# LCD.net
KiCad netlist of a schematic drawn in Altium Designer
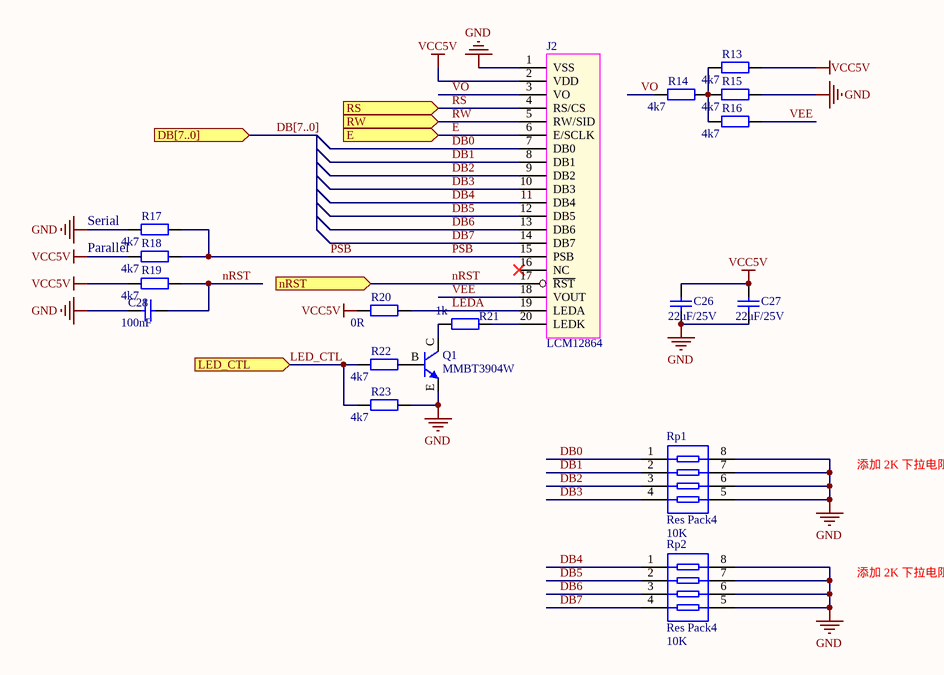
[diagram p0: LCD.SchDoc]

(export (version "E")
  (design (tool "Eeschema 10.0.6"))
  (components
    (comp (ref "C26") (value "22uF/25V") (footprint "C0805") (libsource (lib "myPCB") (part "CAP_08")))
    (comp (ref "C27") (value "22uF/25V") (footprint "C0805") (libsource (lib "myPCB") (part "CAP_08")))
    (comp (ref "C28") (value "100nF") (footprint "R0603") (libsource (lib "MyYX") (part "CAP_04")))
    (comp (ref "J2")
      (value "LCM12864")
      (footprint "LCD12864")
      (description "ST7920/LCM12864")
      (libsource (lib "MyYX") (part "LCM12864"))
    )
    (comp (ref "Q1") (value "MMBT3904W") (footprint "SOT_23") (libsource (lib "MyYX") (part "MMBT3904TT1G")))
    (comp (ref "R13") (value "4k7") (footprint "R0603") (libsource (lib "MyYX") (part "RES_04")))
    (comp (ref "R14") (value "4k7") (footprint "R0603") (libsource (lib "MyYX") (part "RES_04")))
    (comp (ref "R15") (value "4k7") (footprint "R0603") (libsource (lib "MyYX") (part "RES_04")))
    (comp (ref "R16") (value "4k7") (footprint "R0603") (libsource (lib "MyYX") (part "RES_04")))
    (comp (ref "R17") (value "4k7") (footprint "R0603") (libsource (lib "MyYX") (part "RES_04")))
    (comp (ref "R18") (value "4k7") (footprint "R0603") (libsource (lib "MyYX") (part "RES_04")))
    (comp (ref "R19") (value "4k7") (footprint "R0603") (libsource (lib "MyYX") (part "RES_04")))
    (comp (ref "R20") (value "0R") (footprint "R0603") (libsource (lib "MyYX") (part "RES_04")))
    (comp (ref "R21") (value "1k") (footprint "R0603") (libsource (lib "MyYX") (part "RES_04")))
    (comp (ref "R22") (value "4k7") (footprint "R0603") (libsource (lib "MyYX") (part "RES_04")))
    (comp (ref "R23") (value "4k7") (footprint "R0603") (libsource (lib "MyYX") (part "RES_04")))
    (comp (ref "Rp1")
      (value "Res Pack4")
      (footprint "0603X4")
      (fields (field (name "ALTIUM_VALUE") "10K"))
      (libsource (lib "MAX51") (part "Res Pack4"))
    )
    (comp (ref "Rp2")
      (value "Res Pack4")
      (footprint "0603X4")
      (fields (field (name "ALTIUM_VALUE") "10K"))
      (libsource (lib "MAX51") (part "Res Pack4"))
    )
  )
  (nets
    (net (code "1") (name "/DB0") (class "Default")
      (node (ref "J2") (pin "7") (pinfunction "DB0_7") (pintype "passive"))
      (node (ref "Rp1") (pin "1") (pinfunction "1_1") (pintype "passive"))
    )
    (net (code "2") (name "/DB1") (class "Default")
      (node (ref "J2") (pin "8") (pinfunction "DB1_8") (pintype "passive"))
      (node (ref "Rp1") (pin "2") (pinfunction "2_2") (pintype "passive"))
    )
    (net (code "3") (name "/DB2") (class "Default")
      (node (ref "J2") (pin "9") (pinfunction "DB2_9") (pintype "passive"))
      (node (ref "Rp1") (pin "3") (pinfunction "3_3") (pintype "passive"))
    )
    (net (code "4") (name "/DB3") (class "Default")
      (node (ref "J2") (pin "10") (pinfunction "DB3_10") (pintype "passive"))
      (node (ref "Rp1") (pin "4") (pinfunction "4_4") (pintype "passive"))
    )
    (net (code "5") (name "/DB4") (class "Default")
      (node (ref "J2") (pin "11") (pinfunction "DB4_11") (pintype "passive"))
      (node (ref "Rp2") (pin "1") (pinfunction "1_1") (pintype "passive"))
    )
    (net (code "6") (name "/DB5") (class "Default")
      (node (ref "J2") (pin "12") (pinfunction "DB5_12") (pintype "passive"))
      (node (ref "Rp2") (pin "2") (pinfunction "2_2") (pintype "passive"))
    )
    (net (code "7") (name "/DB6") (class "Default")
      (node (ref "J2") (pin "13") (pinfunction "DB6_13") (pintype "passive"))
      (node (ref "Rp2") (pin "3") (pinfunction "3_3") (pintype "passive"))
    )
    (net (code "8") (name "/DB7") (class "Default")
      (node (ref "J2") (pin "14") (pinfunction "DB7_14") (pintype "passive"))
      (node (ref "Rp2") (pin "4") (pinfunction "4_4") (pintype "passive"))
    )
    (net (code "10") (name "/E") (class "Default")
      (node (ref "J2") (pin "6") (pinfunction "E/SCLK_6") (pintype "passive"))
    )
    (net (code "11") (name "/LEDA") (class "Default")
      (node (ref "J2") (pin "19") (pinfunction "LEDA_19") (pintype "passive"))
      (node (ref "R20") (pin "2") (pinfunction "2_2") (pintype "passive"))
    )
    (net (code "12") (name "/LED_CTL") (class "Default")
      (node (ref "R22") (pin "1") (pinfunction "1_1") (pintype "passive"))
      (node (ref "R23") (pin "1") (pinfunction "1_1") (pintype "passive"))
    )
    (net (code "13") (name "/PSB") (class "Default")
      (node (ref "J2") (pin "15") (pinfunction "PSB_15") (pintype "passive"))
      (node (ref "R17") (pin "2") (pinfunction "2_2") (pintype "passive"))
      (node (ref "R18") (pin "2") (pinfunction "2_2") (pintype "passive"))
    )
    (net (code "14") (name "/RS") (class "Default")
      (node (ref "J2") (pin "4") (pinfunction "RS/CS_4") (pintype "passive"))
    )
    (net (code "15") (name "/RW") (class "Default")
      (node (ref "J2") (pin "5") (pinfunction "RW/SID_5") (pintype "passive"))
    )
    (net (code "16") (name "/VEE") (class "Default")
      (node (ref "J2") (pin "18") (pinfunction "VOUT_18") (pintype "passive"))
      (node (ref "R16") (pin "2") (pinfunction "2_2") (pintype "passive"))
    )
    (net (code "17") (name "/VO") (class "Default")
      (node (ref "J2") (pin "3") (pinfunction "VO_3") (pintype "passive"))
      (node (ref "R14") (pin "1") (pinfunction "1_1") (pintype "passive"))
    )
    (net (code "18") (name "/nRST") (class "Default")
      (node (ref "C28") (pin "2") (pinfunction "2_2") (pintype "passive"))
      (node (ref "J2") (pin "17") (pinfunction "~{RST}_17") (pintype "passive"))
      (node (ref "R19") (pin "2") (pinfunction "2_2") (pintype "passive"))
    )
    (net (code "19") (name "GND") (class "Default")
      (node (ref "C26") (pin "1") (pinfunction "1_1") (pintype "passive"))
      (node (ref "C27") (pin "1") (pinfunction "1_1") (pintype "passive"))
      (node (ref "C28") (pin "1") (pinfunction "1_1") (pintype "passive"))
      (node (ref "J2") (pin "1") (pinfunction "VSS_1") (pintype "passive"))
      (node (ref "Q1") (pin "E") (pinfunction "E_E") (pintype "passive"))
      (node (ref "R15") (pin "2") (pinfunction "2_2") (pintype "passive"))
      (node (ref "R17") (pin "1") (pinfunction "1_1") (pintype "passive"))
      (node (ref "R23") (pin "2") (pinfunction "2_2") (pintype "passive"))
      (node (ref "Rp1") (pin "5") (pinfunction "5_5") (pintype "passive"))
      (node (ref "Rp1") (pin "6") (pinfunction "6_6") (pintype "passive"))
      (node (ref "Rp1") (pin "7") (pinfunction "7_7") (pintype "passive"))
      (node (ref "Rp1") (pin "8") (pinfunction "8_8") (pintype "passive"))
      (node (ref "Rp2") (pin "5") (pinfunction "5_5") (pintype "passive"))
      (node (ref "Rp2") (pin "6") (pinfunction "6_6") (pintype "passive"))
      (node (ref "Rp2") (pin "7") (pinfunction "7_7") (pintype "passive"))
      (node (ref "Rp2") (pin "8") (pinfunction "8_8") (pintype "passive"))
    )
    (net (code "20") (name "Net-(J2-LEDK)") (class "Default")
      (node (ref "J2") (pin "20") (pinfunction "LEDK_20") (pintype "passive"))
      (node (ref "R21") (pin "2") (pinfunction "2_2") (pintype "passive"))
    )
    (net (code "21") (name "Net-(Q1-PadB)") (class "Default")
      (node (ref "Q1") (pin "B") (pinfunction "B_B") (pintype "passive"))
      (node (ref "R22") (pin "2") (pinfunction "2_2") (pintype "passive"))
    )
    (net (code "22") (name "Net-(Q1-PadC)") (class "Default")
      (node (ref "Q1") (pin "C") (pinfunction "C_C") (pintype "passive"))
      (node (ref "R21") (pin "1") (pinfunction "1_1") (pintype "passive"))
    )
    (net (code "23") (name "Net-(R13-Pad1)") (class "Default")
      (node (ref "R13") (pin "1") (pinfunction "1_1") (pintype "passive"))
      (node (ref "R14") (pin "2") (pinfunction "2_2") (pintype "passive"))
      (node (ref "R15") (pin "1") (pinfunction "1_1") (pintype "passive"))
      (node (ref "R16") (pin "1") (pinfunction "1_1") (pintype "passive"))
    )
    (net (code "24") (name "VCC5V") (class "Default")
      (node (ref "C26") (pin "2") (pinfunction "2_2") (pintype "passive"))
      (node (ref "C27") (pin "2") (pinfunction "2_2") (pintype "passive"))
      (node (ref "J2") (pin "2") (pinfunction "VDD_2") (pintype "passive"))
      (node (ref "R13") (pin "2") (pinfunction "2_2") (pintype "passive"))
      (node (ref "R18") (pin "1") (pinfunction "1_1") (pintype "passive"))
      (node (ref "R19") (pin "1") (pinfunction "1_1") (pintype "passive"))
      (node (ref "R20") (pin "1") (pinfunction "1_1") (pintype "passive"))
    )
    (net (code "25") (name "unconnected-(J2-NC-Pad16)") (class "Default")
      (node (ref "J2") (pin "16") (pinfunction "NC_16") (pintype "passive+no_connect"))
    )
  )
)
